# fuzz.net
KiCad netlist of a schematic drawn in EAGLE
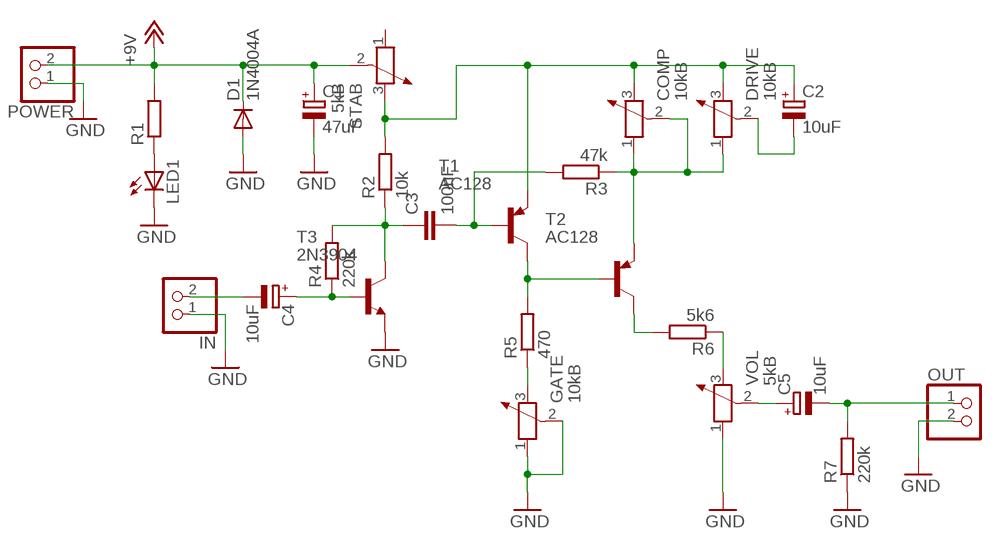
[diagram p0: schematic, sheet 1]

(export (version "E")
  (design (tool "Eeschema 10.0.6"))
  (components
    (comp (ref "C1")
      (value "47uF")
      (footprint "eagle-import:E2,5-6")
      (libsource (lib "eagle-import") (part "CPOL-EUE2.5-6"))
    )
    (comp (ref "C2")
      (value "10uF")
      (footprint "eagle-import:E2,5-6")
      (libsource (lib "eagle-import") (part "CPOL-EUE2.5-6"))
    )
    (comp (ref "C3")
      (value "100nF")
      (footprint "eagle-import:C050-045X075")
      (libsource (lib "eagle-import") (part "C-EU050-045X075"))
    )
    (comp (ref "C4")
      (value "10uF")
      (footprint "eagle-import:E2,5-6")
      (libsource (lib "eagle-import") (part "CPOL-EUE2.5-6"))
    )
    (comp (ref "C5")
      (value "10uF")
      (footprint "eagle-import:E2,5-6")
      (libsource (lib "eagle-import") (part "CPOL-EUE2.5-6"))
    )
    (comp (ref "COMP")
      (value "10kB")
      (footprint "eagle-import:1X03")
      (libsource (lib "eagle-import") (part "POTENTIOMETER_"))
    )
    (comp (ref "D1")
      (value "1N4004A")
      (footprint "eagle-import:DO41-5")
      (libsource (lib "eagle-import") (part "1N4004A"))
    )
    (comp (ref "DRIVE")
      (value "10kB")
      (footprint "eagle-import:1X03")
      (libsource (lib "eagle-import") (part "POTENTIOMETER_"))
    )
    (comp (ref "GATE")
      (value "10kB")
      (footprint "eagle-import:1X03")
      (libsource (lib "eagle-import") (part "POTENTIOMETER_"))
    )
    (comp (ref "IN")
      (value "PINHD-1X2")
      (footprint "eagle-import:1X02")
      (libsource (lib "eagle-import") (part "PINHD-1X2"))
    )
    (comp (ref "LED1")
      (value "LED3MM")
      (footprint "eagle-import:LED3MM")
      (libsource (lib "eagle-import") (part "LED3MM"))
    )
    (comp (ref "OUT")
      (value "PINHD-1X2")
      (footprint "eagle-import:1X02")
      (libsource (lib "eagle-import") (part "PINHD-1X2"))
    )
    (comp (ref "POWER")
      (value "PINHD-1X2")
      (footprint "eagle-import:1X02")
      (libsource (lib "eagle-import") (part "PINHD-1X2"))
    )
    (comp (ref "R1")
      (value "R-EU_")
      (footprint "eagle-import:R0805")
      (libsource (lib "eagle-import") (part "R-EU_"))
    )
    (comp (ref "R2")
      (value "10k")
      (footprint "eagle-import:0207_7")
      (libsource (lib "eagle-import") (part "R-EU_0207/7"))
    )
    (comp (ref "R3")
      (value "47k")
      (footprint "eagle-import:0207_7")
      (libsource (lib "eagle-import") (part "R-EU_0207/7"))
    )
    (comp (ref "R4")
      (value "220k")
      (footprint "eagle-import:0207_7")
      (libsource (lib "eagle-import") (part "R-EU_0207/7"))
    )
    (comp (ref "R5")
      (value "470")
      (footprint "eagle-import:0207_7")
      (libsource (lib "eagle-import") (part "R-EU_0207/7"))
    )
    (comp (ref "R6")
      (value "5k6")
      (footprint "eagle-import:0207_7")
      (libsource (lib "eagle-import") (part "R-EU_0207/7"))
    )
    (comp (ref "R7")
      (value "220k")
      (footprint "eagle-import:0207_7")
      (libsource (lib "eagle-import") (part "R-EU_0207/7"))
    )
    (comp (ref "STAB")
      (value "5kB")
      (footprint "eagle-import:1X03")
      (libsource (lib "eagle-import") (part "POTENTIOMETER_"))
    )
    (comp (ref "T1")
      (value "AC128")
      (footprint "eagle-import:TO18")
      (libsource (lib "eagle-import") (part "AC128"))
    )
    (comp (ref "T2")
      (value "AC128")
      (footprint "eagle-import:TO18")
      (libsource (lib "eagle-import") (part "AC128"))
    )
    (comp (ref "T3")
      (value "2N3904")
      (footprint "eagle-import:TO92")
      (libsource (lib "eagle-import") (part "2N3904"))
    )
    (comp (ref "VOL")
      (value "5kB")
      (footprint "eagle-import:1X03")
      (libsource (lib "eagle-import") (part "POTENTIOMETER_"))
    )
  )
  (nets
    (net (code "1") (name "+9V") (class "Default")
      (node (ref "C1") (pin "+") (pinfunction "+_+") (pintype "passive"))
      (node (ref "D1") (pin "C") (pinfunction "C_C") (pintype "passive"))
      (node (ref "POWER") (pin "2") (pinfunction "2_2") (pintype "passive"))
      (node (ref "R1") (pin "2") (pinfunction "2_2") (pintype "passive"))
      (node (ref "STAB") (pin "2") (pinfunction "3_2") (pintype "passive"))
    )
    (net (code "2") (name "GND") (class "Default")
      (node (ref "C1") (pin "-") (pinfunction "-_-") (pintype "passive"))
      (node (ref "D1") (pin "A") (pinfunction "A_A") (pintype "passive"))
      (node (ref "GATE") (pin "1") (pinfunction "1_1") (pintype "passive"))
      (node (ref "GATE") (pin "2") (pinfunction "3_2") (pintype "passive"))
      (node (ref "IN") (pin "1") (pinfunction "1_1") (pintype "passive"))
      (node (ref "LED1") (pin "K") (pinfunction "C_K") (pintype "passive"))
      (node (ref "OUT") (pin "2") (pinfunction "2_2") (pintype "passive"))
      (node (ref "POWER") (pin "1") (pinfunction "1_1") (pintype "passive"))
      (node (ref "R7") (pin "1") (pinfunction "1_1") (pintype "passive"))
      (node (ref "T3") (pin "3") (pinfunction "E_3") (pintype "passive"))
      (node (ref "VOL") (pin "1") (pinfunction "1_1") (pintype "passive"))
    )
    (net (code "3") (name "Net-(C4-Pad-)") (class "Default")
      (node (ref "C4") (pin "-") (pinfunction "-_-") (pintype "passive"))
      (node (ref "IN") (pin "2") (pinfunction "2_2") (pintype "passive"))
    )
    (net (code "4") (name "Net-(C5-Pad-)") (class "Default")
      (node (ref "C5") (pin "-") (pinfunction "-_-") (pintype "passive"))
      (node (ref "OUT") (pin "1") (pinfunction "1_1") (pintype "passive"))
      (node (ref "R7") (pin "2") (pinfunction "2_2") (pintype "passive"))
    )
    (net (code "5") (name "Net-(COMP-2)") (class "Default")
      (node (ref "C2") (pin "+") (pinfunction "+_+") (pintype "passive"))
      (node (ref "COMP") (pin "3") (pinfunction "2_3") (pintype "passive"))
      (node (ref "DRIVE") (pin "3") (pinfunction "2_3") (pintype "passive"))
      (node (ref "R2") (pin "2") (pinfunction "2_2") (pintype "passive"))
      (node (ref "STAB") (pin "3") (pinfunction "2_3") (pintype "passive"))
      (node (ref "T1") (pin "1") (pinfunction "E_1") (pintype "passive"))
    )
    (net (code "6") (name "Net-(COMP-3)") (class "Default")
      (node (ref "COMP") (pin "1") (pinfunction "1_1") (pintype "passive"))
      (node (ref "COMP") (pin "2") (pinfunction "3_2") (pintype "passive"))
      (node (ref "DRIVE") (pin "1") (pinfunction "1_1") (pintype "passive"))
      (node (ref "R3") (pin "1") (pinfunction "1_1") (pintype "passive"))
      (node (ref "T2") (pin "1") (pinfunction "E_1") (pintype "passive"))
    )
    (net (code "7") (name "Net-(DRIVE-3)") (class "Default")
      (node (ref "C2") (pin "-") (pinfunction "-_-") (pintype "passive"))
      (node (ref "DRIVE") (pin "2") (pinfunction "3_2") (pintype "passive"))
    )
    (net (code "8") (name "Net-(GATE-2)") (class "Default")
      (node (ref "GATE") (pin "3") (pinfunction "2_3") (pintype "passive"))
      (node (ref "R5") (pin "1") (pinfunction "1_1") (pintype "passive"))
    )
    (net (code "9") (name "Net-(LED1-PadA)") (class "Default")
      (node (ref "LED1") (pin "A") (pinfunction "A_A") (pintype "passive"))
      (node (ref "R1") (pin "1") (pinfunction "1_1") (pintype "passive"))
    )
    (net (code "10") (name "Net-(T1-B)") (class "Default")
      (node (ref "C3") (pin "2") (pinfunction "2_2") (pintype "passive"))
      (node (ref "R3") (pin "2") (pinfunction "2_2") (pintype "passive"))
      (node (ref "T1") (pin "2") (pinfunction "B_2") (pintype "passive"))
    )
    (net (code "11") (name "Net-(T1-C)") (class "Default")
      (node (ref "R5") (pin "2") (pinfunction "2_2") (pintype "passive"))
      (node (ref "T1") (pin "3") (pinfunction "C_3") (pintype "passive"))
      (node (ref "T2") (pin "2") (pinfunction "B_2") (pintype "passive"))
    )
    (net (code "12") (name "Net-(T2-C)") (class "Default")
      (node (ref "R6") (pin "2") (pinfunction "2_2") (pintype "passive"))
      (node (ref "T2") (pin "3") (pinfunction "C_3") (pintype "passive"))
    )
    (net (code "13") (name "Net-(T3-B)") (class "Default")
      (node (ref "C4") (pin "+") (pinfunction "+_+") (pintype "passive"))
      (node (ref "R4") (pin "1") (pinfunction "1_1") (pintype "passive"))
      (node (ref "T3") (pin "2") (pinfunction "B_2") (pintype "passive"))
    )
    (net (code "14") (name "Net-(T3-C)") (class "Default")
      (node (ref "C3") (pin "1") (pinfunction "1_1") (pintype "passive"))
      (node (ref "R2") (pin "1") (pinfunction "1_1") (pintype "passive"))
      (node (ref "R4") (pin "2") (pinfunction "2_2") (pintype "passive"))
      (node (ref "T3") (pin "1") (pinfunction "C_1") (pintype "passive"))
    )
    (net (code "15") (name "Net-(VOL-2)") (class "Default")
      (node (ref "R6") (pin "1") (pinfunction "1_1") (pintype "passive"))
      (node (ref "VOL") (pin "3") (pinfunction "2_3") (pintype "passive"))
    )
    (net (code "16") (name "Net-(VOL-3)") (class "Default")
      (node (ref "C5") (pin "+") (pinfunction "+_+") (pintype "passive"))
      (node (ref "VOL") (pin "2") (pinfunction "3_2") (pintype "passive"))
    )
    (net (code "17") (name "unconnected-(STAB-Pad1)") (class "Default")
      (node (ref "STAB") (pin "1") (pinfunction "1_1") (pintype "passive"))
    )
  )
)
